# FMC_connector.net
KiCad netlist of a schematic drawn in Altium Designer
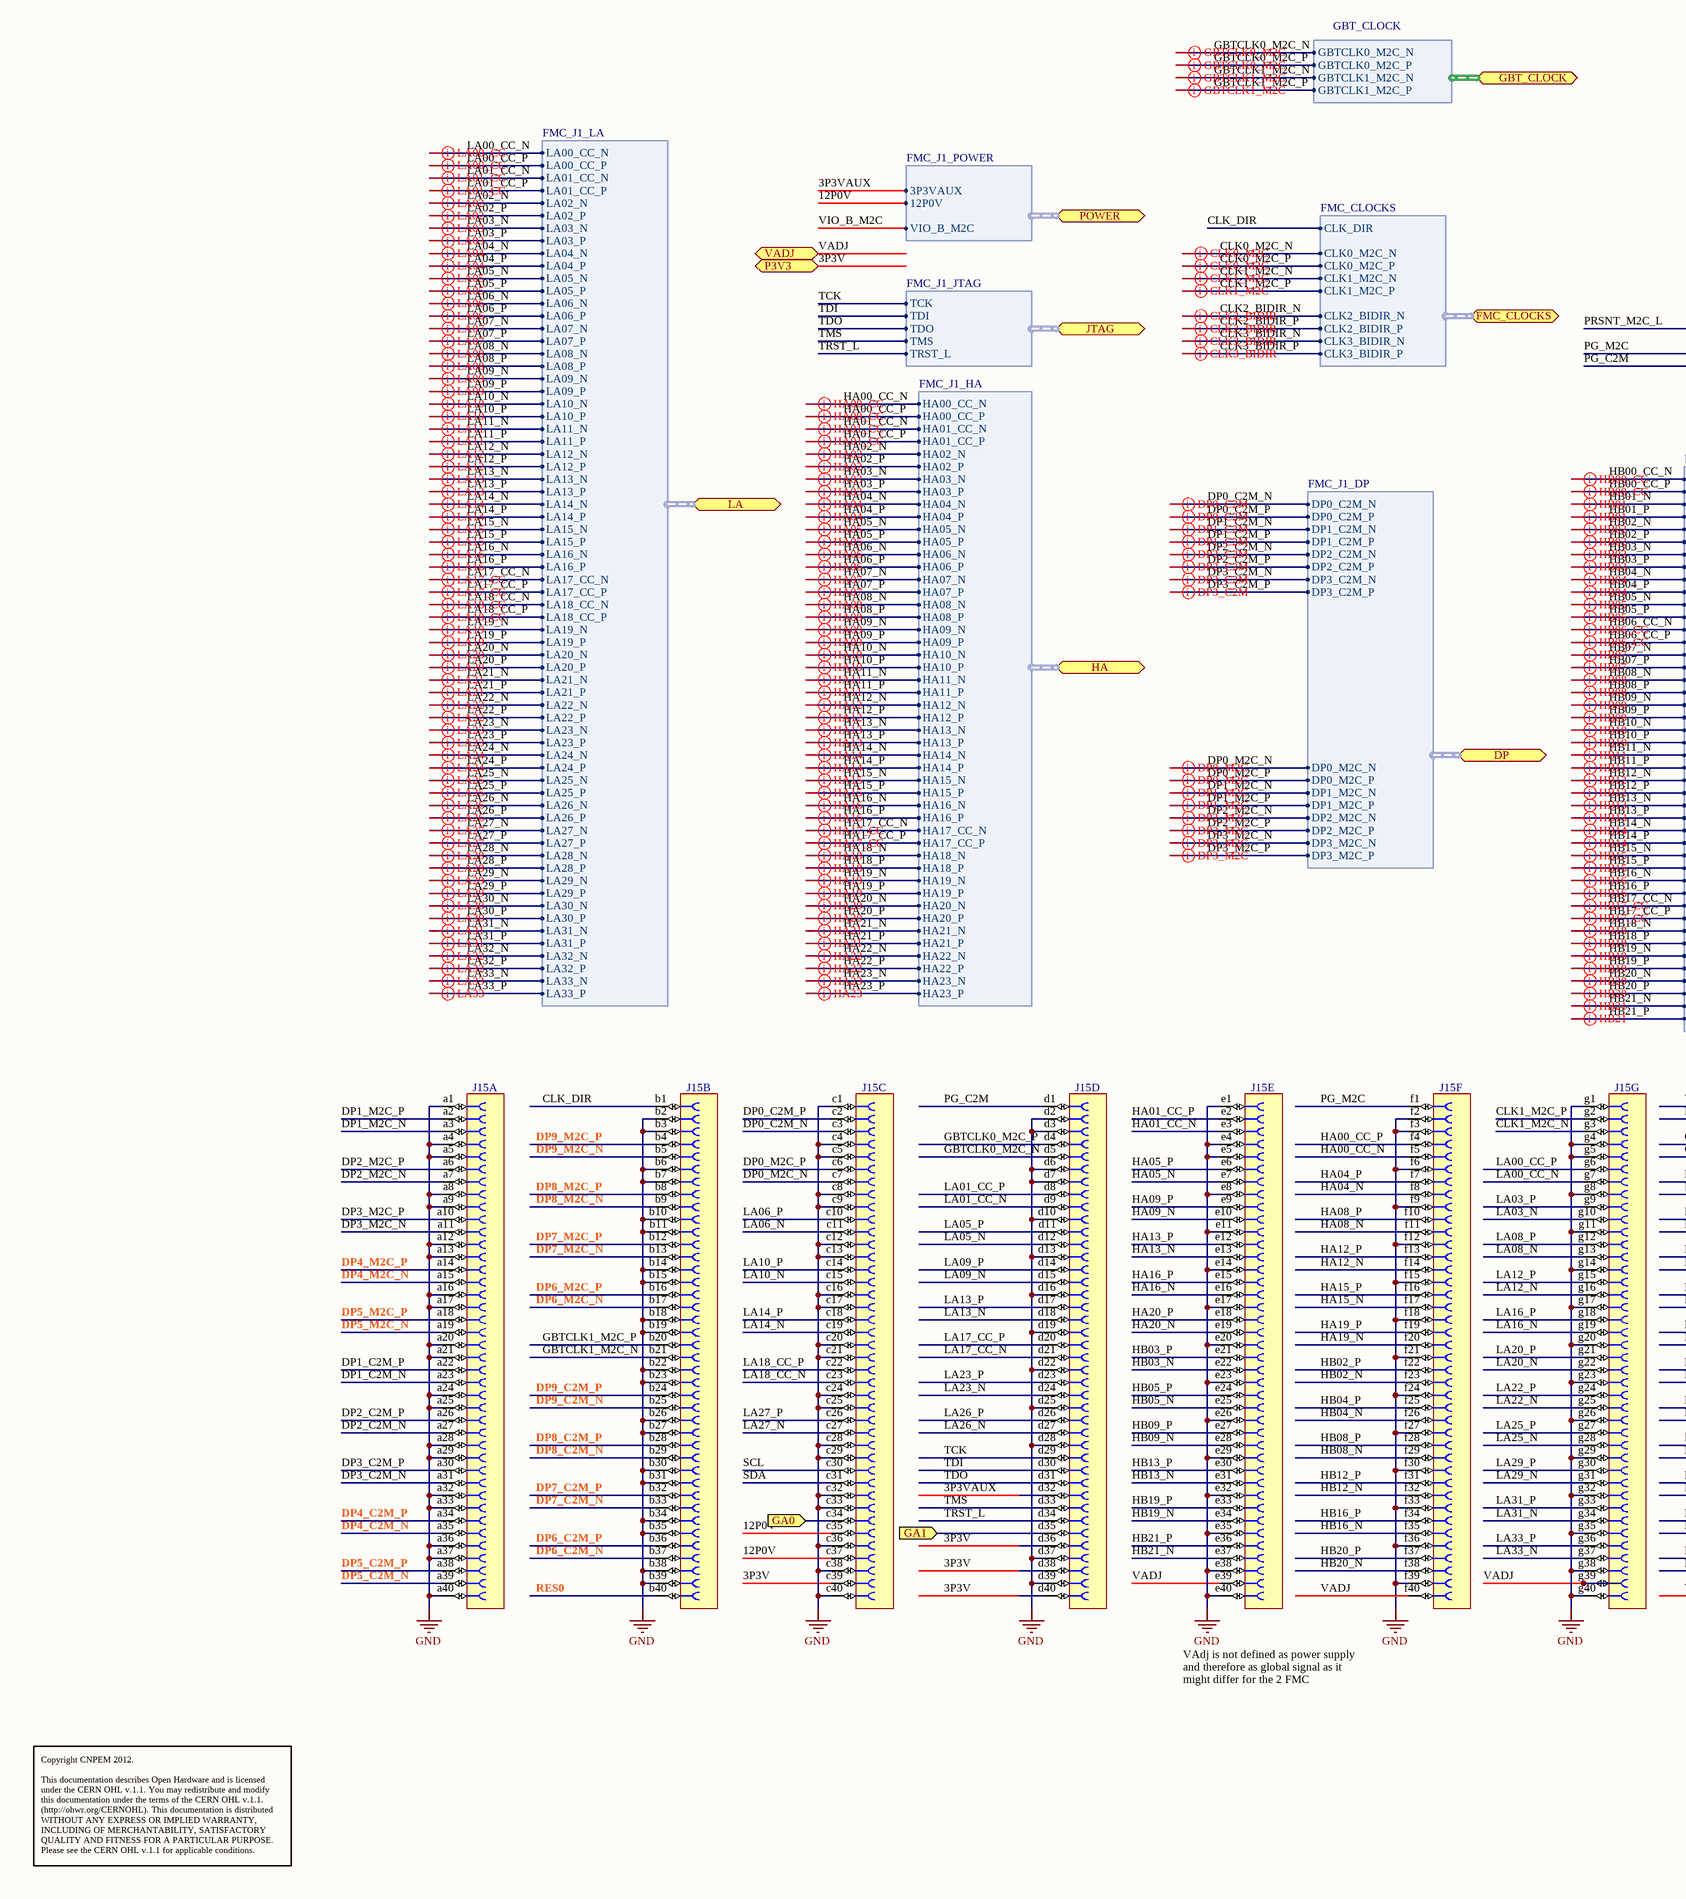
[diagram p0: FMC_connector.SchDoc, left]
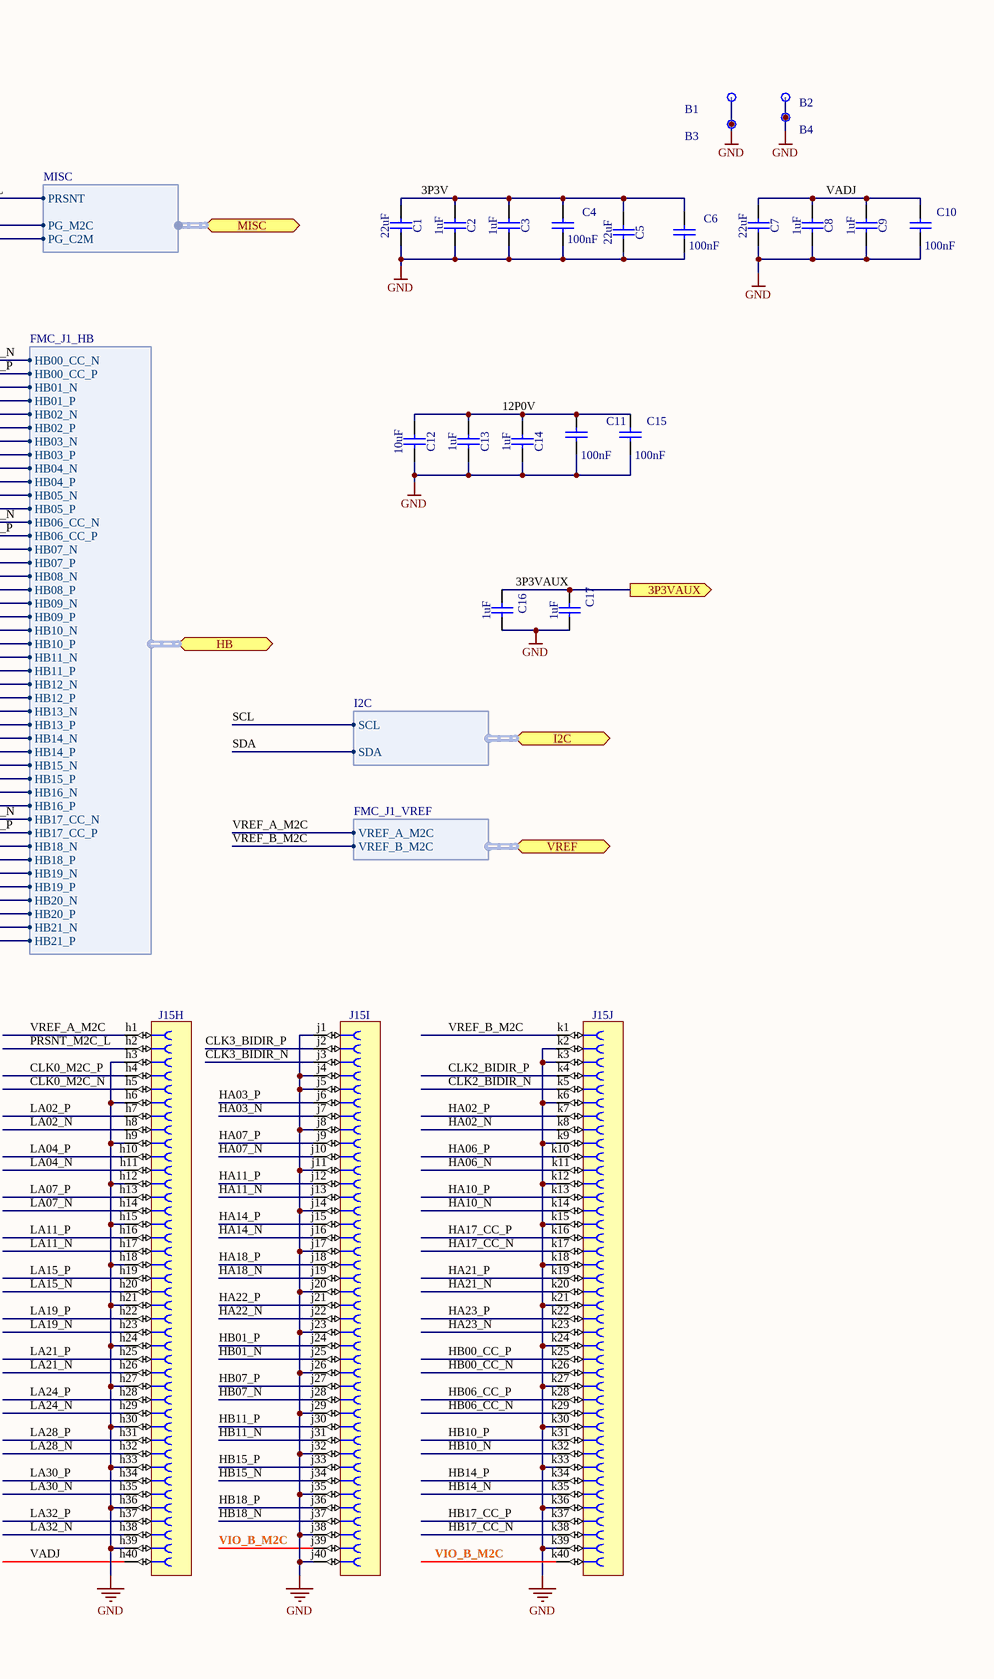
[diagram p1: FMC_connector.SchDoc, right]

(export (version "E")
  (design (tool "Eeschema 10.0.6"))
  (components
    (comp (ref "B1")
      (value "Plated Hole")
      (footprint "MTG270_500")
      (description "Single Terminal Socket")
      (fields (field (name "PART NUMBER") "PLATED_HOLE2.7_PAD5.0") (field (name "AUTHOR") "CERN DEM JMW"))
      (libsource (lib "Eletro-mechanical") (part "Single Terminal Socket"))
    )
    (comp (ref "B2")
      (value "Plated Hole")
      (footprint "MTG270_500")
      (description "Single Terminal Socket")
      (fields (field (name "PART NUMBER") "PLATED_HOLE2.7_PAD5.0") (field (name "AUTHOR") "CERN DEM JMW"))
      (libsource (lib "Eletro-mechanical") (part "Single Terminal Socket"))
    )
    (comp (ref "B3")
      (value "Plated Hole")
      (footprint "MTG270_500")
      (description "Single Terminal Socket")
      (fields (field (name "PART NUMBER") "PLATED_HOLE2.7_PAD5.0") (field (name "AUTHOR") "CERN DEM JMW"))
      (libsource (lib "Eletro-mechanical") (part "Single Terminal Socket"))
    )
    (comp (ref "B4")
      (value "Plated Hole")
      (footprint "MTG270_500")
      (description "Single Terminal Socket")
      (fields (field (name "PART NUMBER") "PLATED_HOLE2.7_PAD5.0") (field (name "AUTHOR") "CERN DEM JMW"))
      (libsource (lib "Eletro-mechanical") (part "Single Terminal Socket"))
    )
    (comp (ref "C1")
      (value "22uF")
      (footprint "CAPC3216X180N")
      (description "Non-polarised capacitor")
      (fields
        (field (name "PART NUMBER") "CC1206_22UF_10V_10%_X7R")
        (field (name "VOLTAGE") "10V")
        (field (name "AUTHOR") "CERN DEM JLC")
      )
      (libsource (lib "Capacitors") (part "Capacitor - non polarized"))
    )
    (comp (ref "C2")
      (value "1uF")
      (footprint "CAPC1608X87N")
      (description "Non-polarised capacitor")
      (fields
        (field (name "PART NUMBER") "CC0603_1UF_16V_10%_X7R")
        (field (name "VOLTAGE") "16V")
        (field (name "AUTHOR") "CERN DEM JLC")
      )
      (libsource (lib "Capacitors") (part "Capacitor - non polarized"))
    )
    (comp (ref "C3")
      (value "1uF")
      (footprint "CAPC1608X87N")
      (description "Non-polarised capacitor")
      (fields
        (field (name "PART NUMBER") "CC0603_1UF_16V_10%_X7R")
        (field (name "VOLTAGE") "16V")
        (field (name "AUTHOR") "CERN DEM JLC")
      )
      (libsource (lib "Capacitors") (part "Capacitor - non polarized"))
    )
    (comp (ref "C4")
      (value "100nF")
      (footprint "CAPC0603X33N")
      (description "Non-polarised capacitor")
      (fields
        (field (name "PART NUMBER") "CC0201_100NF_6.3V_10%_X5R")
        (field (name "VOLTAGE") "6.3V")
        (field (name "AUTHOR") "CERN DEM JLC")
      )
      (libsource (lib "Capacitors") (part "Capacitor - non polarized"))
    )
    (comp (ref "C5")
      (value "22uF")
      (footprint "CAPC3216X180N")
      (description "Non-polarised capacitor")
      (fields
        (field (name "PART NUMBER") "CC1206_22UF_10V_10%_X7R")
        (field (name "VOLTAGE") "10V")
        (field (name "AUTHOR") "CERN DEM JLC")
      )
      (libsource (lib "Capacitors") (part "Capacitor - non polarized"))
    )
    (comp (ref "C6")
      (value "100nF")
      (footprint "CAPC0603X33N")
      (description "Non-polarised capacitor")
      (fields
        (field (name "PART NUMBER") "CC0201_100NF_6.3V_10%_X5R")
        (field (name "VOLTAGE") "6.3V")
        (field (name "AUTHOR") "CERN DEM JLC")
      )
      (libsource (lib "Capacitors") (part "Capacitor - non polarized"))
    )
    (comp (ref "C7")
      (value "22uF")
      (footprint "CAPC3216X180N")
      (description "Non-polarised capacitor")
      (fields
        (field (name "PART NUMBER") "CC1206_22UF_10V_10%_X7R")
        (field (name "VOLTAGE") "10V")
        (field (name "AUTHOR") "CERN DEM JLC")
      )
      (libsource (lib "Capacitors") (part "Capacitor - non polarized"))
    )
    (comp (ref "C8")
      (value "1uF")
      (footprint "CAPC1608X87N")
      (description "Non-polarised capacitor")
      (fields
        (field (name "PART NUMBER") "CC0603_1UF_16V_10%_X7R")
        (field (name "VOLTAGE") "16V")
        (field (name "AUTHOR") "CERN DEM JLC")
      )
      (libsource (lib "Capacitors") (part "Capacitor - non polarized"))
    )
    (comp (ref "C9")
      (value "1uF")
      (footprint "CAPC1608X87N")
      (description "Non-polarised capacitor")
      (fields
        (field (name "PART NUMBER") "CC0603_1UF_16V_10%_X7R")
        (field (name "VOLTAGE") "16V")
        (field (name "AUTHOR") "CERN DEM JLC")
      )
      (libsource (lib "Capacitors") (part "Capacitor - non polarized"))
    )
    (comp (ref "C10")
      (value "100nF")
      (footprint "CAPC0603X33N")
      (description "Non-polarised capacitor")
      (fields
        (field (name "PART NUMBER") "CC0201_100NF_6.3V_10%_X5R")
        (field (name "VOLTAGE") "6.3V")
        (field (name "AUTHOR") "CERN DEM JLC")
      )
      (libsource (lib "Capacitors") (part "Capacitor - non polarized"))
    )
    (comp (ref "C11")
      (value "100nF")
      (footprint "CAPC0603X33N")
      (description "Non-polarised capacitor")
      (fields
        (field (name "PART NUMBER") "CC0201_100NF_6.3V_10%_X5R")
        (field (name "VOLTAGE") "6.3V")
        (field (name "AUTHOR") "CERN DEM JLC")
      )
      (libsource (lib "Capacitors") (part "Capacitor - non polarized"))
    )
    (comp (ref "C12")
      (value "10uF")
      (footprint "CAPC2012X135N")
      (description "Non-polarised capacitor")
      (fields
        (field (name "PART NUMBER") "CC0805_10UF_16V_10%_X5R")
        (field (name "VOLTAGE") "16V")
        (field (name "AUTHOR") "CERN DEM JLC")
      )
      (libsource (lib "Capacitors") (part "Capacitor - non polarized"))
    )
    (comp (ref "C13")
      (value "1uF")
      (footprint "CAPC1608X87N")
      (description "Non-polarised capacitor")
      (fields
        (field (name "PART NUMBER") "CC0603_1UF_16V_10%_X7R")
        (field (name "VOLTAGE") "16V")
        (field (name "AUTHOR") "CERN DEM JLC")
      )
      (libsource (lib "Capacitors") (part "Capacitor - non polarized"))
    )
    (comp (ref "C14")
      (value "1uF")
      (footprint "CAPC1608X87N")
      (description "Non-polarised capacitor")
      (fields
        (field (name "PART NUMBER") "CC0603_1UF_16V_10%_X7R")
        (field (name "VOLTAGE") "16V")
        (field (name "AUTHOR") "CERN DEM JLC")
      )
      (libsource (lib "Capacitors") (part "Capacitor - non polarized"))
    )
    (comp (ref "C15")
      (value "100nF")
      (footprint "CAPC0603X33N")
      (description "Non-polarised capacitor")
      (fields
        (field (name "PART NUMBER") "CC0201_100NF_6.3V_10%_X5R")
        (field (name "VOLTAGE") "6.3V")
        (field (name "AUTHOR") "CERN DEM JLC")
      )
      (libsource (lib "Capacitors") (part "Capacitor - non polarized"))
    )
    (comp (ref "C16")
      (value "1uF")
      (footprint "CAPC1608X87N")
      (description "Non-polarised capacitor")
      (fields
        (field (name "PART NUMBER") "CC0603_1UF_16V_10%_X7R")
        (field (name "VOLTAGE") "16V")
        (field (name "AUTHOR") "CERN DEM JLC")
      )
      (libsource (lib "Capacitors") (part "Capacitor - non polarized"))
    )
    (comp (ref "C17")
      (value "1uF")
      (footprint "CAPC1608X87N")
      (description "Non-polarised capacitor")
      (fields
        (field (name "PART NUMBER") "CC0603_1UF_16V_10%_X7R")
        (field (name "VOLTAGE") "16V")
        (field (name "AUTHOR") "CERN DEM JLC")
      )
      (libsource (lib "Capacitors") (part "Capacitor - non polarized"))
    )
    (comp (ref "J15")
      (value "VITA 57")
      (footprint "SAMTEC_ASP-134486-01")
      (description "Connector VITA 57, 400 Female contacts in 10 row abcdefghj")
      (fields
        (field (name "PART NUMBER") "SAMTEC_ASP-134486-01")
        (field (name "MANUFACTURER") "SAMTEC")
        (field (name "AUTHOR") "CERN DEM JLC")
      )
      (libsource (lib "Connectors") (part "Connector VITA 57 400 Female (abcdefghjk)"))
    )
  )
  (nets
    (net (code "12") (name "/3P3V") (class "Default")
      (node (ref "C1") (pin "1") (pinfunction "1_1") (pintype "passive"))
      (node (ref "C2") (pin "1") (pinfunction "1_1") (pintype "passive"))
      (node (ref "C3") (pin "1") (pinfunction "1_1") (pintype "passive"))
      (node (ref "C4") (pin "2") (pinfunction "2_2") (pintype "passive"))
      (node (ref "C5") (pin "1") (pinfunction "1_1") (pintype "passive"))
      (node (ref "C6") (pin "2") (pinfunction "2_2") (pintype "passive"))
      (node (ref "J15") (pin "c39") (pinfunction "c39_c39") (pintype "bidirectional"))
      (node (ref "J15") (pin "d36") (pinfunction "d36_d36") (pintype "bidirectional"))
      (node (ref "J15") (pin "d38") (pinfunction "d38_d38") (pintype "bidirectional"))
      (node (ref "J15") (pin "d40") (pinfunction "d40_d40") (pintype "bidirectional"))
    )
    (net (code "13") (name "/3P3VAUX") (class "Default")
      (node (ref "C16") (pin "1") (pinfunction "1_1") (pintype "passive"))
      (node (ref "C17") (pin "1") (pinfunction "1_1") (pintype "passive"))
      (node (ref "J15") (pin "d32") (pinfunction "d32_d32") (pintype "bidirectional"))
    )
    (net (code "14") (name "/12P0V") (class "Default")
      (node (ref "C11") (pin "2") (pinfunction "2_2") (pintype "passive"))
      (node (ref "C12") (pin "1") (pinfunction "1_1") (pintype "passive"))
      (node (ref "C13") (pin "1") (pinfunction "1_1") (pintype "passive"))
      (node (ref "C14") (pin "1") (pinfunction "1_1") (pintype "passive"))
      (node (ref "C15") (pin "2") (pinfunction "2_2") (pintype "passive"))
      (node (ref "J15") (pin "c35") (pinfunction "c35_c35") (pintype "bidirectional"))
      (node (ref "J15") (pin "c37") (pinfunction "c37_c37") (pintype "bidirectional"))
    )
    (net (code "15") (name "/CLK0_M2C_N") (class "Default")
      (node (ref "J15") (pin "h5") (pinfunction "h5_h5") (pintype "bidirectional"))
    )
    (net (code "16") (name "/CLK0_M2C_P") (class "Default")
      (node (ref "J15") (pin "h4") (pinfunction "h4_h4") (pintype "bidirectional"))
    )
    (net (code "17") (name "/CLK1_M2C_N") (class "Default")
      (node (ref "J15") (pin "g3") (pinfunction "g3_g3") (pintype "bidirectional"))
    )
    (net (code "18") (name "/CLK1_M2C_P") (class "Default")
      (node (ref "J15") (pin "g2") (pinfunction "g2_g2") (pintype "bidirectional"))
    )
    (net (code "19") (name "/CLK2_BIDIR_N") (class "Default")
      (node (ref "J15") (pin "k5") (pinfunction "k5_k5") (pintype "bidirectional"))
    )
    (net (code "20") (name "/CLK2_BIDIR_P") (class "Default")
      (node (ref "J15") (pin "k4") (pinfunction "k4_k4") (pintype "bidirectional"))
    )
    (net (code "21") (name "/CLK3_BIDIR_N") (class "Default")
      (node (ref "J15") (pin "j3") (pinfunction "j3_j3") (pintype "bidirectional"))
    )
    (net (code "22") (name "/CLK3_BIDIR_P") (class "Default")
      (node (ref "J15") (pin "j2") (pinfunction "j2_j2") (pintype "bidirectional"))
    )
    (net (code "23") (name "/CLK_DIR") (class "Default")
      (node (ref "J15") (pin "b1") (pinfunction "b1_b1") (pintype "bidirectional"))
    )
    (net (code "24") (name "/DP0_C2M_N") (class "Default")
      (node (ref "J15") (pin "c3") (pinfunction "c3_c3") (pintype "bidirectional"))
    )
    (net (code "25") (name "/DP0_C2M_P") (class "Default")
      (node (ref "J15") (pin "c2") (pinfunction "c2_c2") (pintype "bidirectional"))
    )
    (net (code "26") (name "/DP0_M2C_N") (class "Default")
      (node (ref "J15") (pin "c7") (pinfunction "c7_c7") (pintype "bidirectional"))
    )
    (net (code "27") (name "/DP0_M2C_P") (class "Default")
      (node (ref "J15") (pin "c6") (pinfunction "c6_c6") (pintype "bidirectional"))
    )
    (net (code "28") (name "/DP1_C2M_N") (class "Default")
      (node (ref "J15") (pin "a23") (pinfunction "a23_a23") (pintype "bidirectional"))
    )
    (net (code "29") (name "/DP1_C2M_P") (class "Default")
      (node (ref "J15") (pin "a22") (pinfunction "a22_a22") (pintype "bidirectional"))
    )
    (net (code "30") (name "/DP1_M2C_N") (class "Default")
      (node (ref "J15") (pin "a3") (pinfunction "a3_a3") (pintype "bidirectional"))
    )
    (net (code "31") (name "/DP1_M2C_P") (class "Default")
      (node (ref "J15") (pin "a2") (pinfunction "a2_a2") (pintype "bidirectional"))
    )
    (net (code "32") (name "/DP2_C2M_N") (class "Default")
      (node (ref "J15") (pin "a27") (pinfunction "a27_a27") (pintype "bidirectional"))
    )
    (net (code "33") (name "/DP2_C2M_P") (class "Default")
      (node (ref "J15") (pin "a26") (pinfunction "a26_a26") (pintype "bidirectional"))
    )
    (net (code "34") (name "/DP2_M2C_N") (class "Default")
      (node (ref "J15") (pin "a7") (pinfunction "a7_a7") (pintype "bidirectional"))
    )
    (net (code "35") (name "/DP2_M2C_P") (class "Default")
      (node (ref "J15") (pin "a6") (pinfunction "a6_a6") (pintype "bidirectional"))
    )
    (net (code "36") (name "/DP3_C2M_N") (class "Default")
      (node (ref "J15") (pin "a31") (pinfunction "a31_a31") (pintype "bidirectional"))
    )
    (net (code "37") (name "/DP3_C2M_P") (class "Default")
      (node (ref "J15") (pin "a30") (pinfunction "a30_a30") (pintype "bidirectional"))
    )
    (net (code "38") (name "/DP3_M2C_N") (class "Default")
      (node (ref "J15") (pin "a11") (pinfunction "a11_a11") (pintype "bidirectional"))
    )
    (net (code "39") (name "/DP3_M2C_P") (class "Default")
      (node (ref "J15") (pin "a10") (pinfunction "a10_a10") (pintype "bidirectional"))
    )
    (net (code "40") (name "/GA0") (class "Default")
      (node (ref "J15") (pin "c34") (pinfunction "c34_c34") (pintype "bidirectional"))
    )
    (net (code "41") (name "/GA1") (class "Default")
      (node (ref "J15") (pin "d35") (pinfunction "d35_d35") (pintype "bidirectional"))
    )
    (net (code "42") (name "/GBTCLK0_M2C_N") (class "Default")
      (node (ref "J15") (pin "d5") (pinfunction "d5_d5") (pintype "bidirectional"))
    )
    (net (code "43") (name "/GBTCLK0_M2C_P") (class "Default")
      (node (ref "J15") (pin "d4") (pinfunction "d4_d4") (pintype "bidirectional"))
    )
    (net (code "44") (name "/GBTCLK1_M2C_N") (class "Default")
      (node (ref "J15") (pin "b21") (pinfunction "b21_b21") (pintype "bidirectional"))
    )
    (net (code "45") (name "/GBTCLK1_M2C_P") (class "Default")
      (node (ref "J15") (pin "b20") (pinfunction "b20_b20") (pintype "bidirectional"))
    )
    (net (code "46") (name "/HA00_CC_N") (class "Default")
      (node (ref "J15") (pin "f5") (pinfunction "f5_f5") (pintype "bidirectional"))
    )
    (net (code "47") (name "/HA00_CC_P") (class "Default")
      (node (ref "J15") (pin "f4") (pinfunction "f4_f4") (pintype "bidirectional"))
    )
    (net (code "48") (name "/HA01_CC_N") (class "Default")
      (node (ref "J15") (pin "e3") (pinfunction "e3_e3") (pintype "bidirectional"))
    )
    (net (code "49") (name "/HA01_CC_P") (class "Default")
      (node (ref "J15") (pin "e2") (pinfunction "e2_e2") (pintype "bidirectional"))
    )
    (net (code "50") (name "/HA02_N") (class "Default")
      (node (ref "J15") (pin "k8") (pinfunction "k8_k8") (pintype "bidirectional"))
    )
    (net (code "51") (name "/HA02_P") (class "Default")
      (node (ref "J15") (pin "k7") (pinfunction "k7_k7") (pintype "bidirectional"))
    )
    (net (code "52") (name "/HA03_N") (class "Default")
      (node (ref "J15") (pin "j7") (pinfunction "j7_j7") (pintype "bidirectional"))
    )
    (net (code "53") (name "/HA03_P") (class "Default")
      (node (ref "J15") (pin "j6") (pinfunction "j6_j6") (pintype "bidirectional"))
    )
    (net (code "54") (name "/HA04_N") (class "Default")
      (node (ref "J15") (pin "f8") (pinfunction "f8_f8") (pintype "bidirectional"))
    )
    (net (code "55") (name "/HA04_P") (class "Default")
      (node (ref "J15") (pin "f7") (pinfunction "f7_f7") (pintype "bidirectional"))
    )
    (net (code "56") (name "/HA05_N") (class "Default")
      (node (ref "J15") (pin "e7") (pinfunction "e7_e7") (pintype "bidirectional"))
    )
    (net (code "57") (name "/HA05_P") (class "Default")
      (node (ref "J15") (pin "e6") (pinfunction "e6_e6") (pintype "bidirectional"))
    )
    (net (code "58") (name "/HA06_N") (class "Default")
      (node (ref "J15") (pin "k11") (pinfunction "k11_k11") (pintype "bidirectional"))
    )
    (net (code "59") (name "/HA06_P") (class "Default")
      (node (ref "J15") (pin "k10") (pinfunction "k10_k10") (pintype "bidirectional"))
    )
    (net (code "60") (name "/HA07_N") (class "Default")
      (node (ref "J15") (pin "j10") (pinfunction "j10_j10") (pintype "bidirectional"))
    )
    (net (code "61") (name "/HA07_P") (class "Default")
      (node (ref "J15") (pin "j9") (pinfunction "j9_j9") (pintype "bidirectional"))
    )
    (net (code "62") (name "/HA08_N") (class "Default")
      (node (ref "J15") (pin "f11") (pinfunction "f11_f11") (pintype "bidirectional"))
    )
    (net (code "63") (name "/HA08_P") (class "Default")
      (node (ref "J15") (pin "f10") (pinfunction "f10_f10") (pintype "bidirectional"))
    )
    (net (code "64") (name "/HA09_N") (class "Default")
      (node (ref "J15") (pin "e10") (pinfunction "e10_e10") (pintype "bidirectional"))
    )
    (net (code "65") (name "/HA09_P") (class "Default")
      (node (ref "J15") (pin "e9") (pinfunction "e9_e9") (pintype "bidirectional"))
    )
    (net (code "66") (name "/HA10_N") (class "Default")
      (node (ref "J15") (pin "k14") (pinfunction "k14_k14") (pintype "bidirectional"))
    )
    (net (code "67") (name "/HA10_P") (class "Default")
      (node (ref "J15") (pin "k13") (pinfunction "k13_k13") (pintype "bidirectional"))
    )
    (net (code "68") (name "/HA11_N") (class "Default")
      (node (ref "J15") (pin "j13") (pinfunction "j13_j13") (pintype "bidirectional"))
    )
    (net (code "69") (name "/HA11_P") (class "Default")
      (node (ref "J15") (pin "j12") (pinfunction "j12_j12") (pintype "bidirectional"))
    )
    (net (code "70") (name "/HA12_N") (class "Default")
      (node (ref "J15") (pin "f14") (pinfunction "f14_f14") (pintype "bidirectional"))
    )
    (net (code "71") (name "/HA12_P") (class "Default")
      (node (ref "J15") (pin "f13") (pinfunction "f13_f13") (pintype "bidirectional"))
    )
    (net (code "72") (name "/HA13_N") (class "Default")
      (node (ref "J15") (pin "e13") (pinfunction "e13_e13") (pintype "bidirectional"))
    )
    (net (code "73") (name "/HA13_P") (class "Default")
      (node (ref "J15") (pin "e12") (pinfunction "e12_e12") (pintype "bidirectional"))
    )
    (net (code "74") (name "/HA14_N") (class "Default")
      (node (ref "J15") (pin "j16") (pinfunction "j16_j16") (pintype "bidirectional"))
    )
    (net (code "75") (name "/HA14_P") (class "Default")
      (node (ref "J15") (pin "j15") (pinfunction "j15_j15") (pintype "bidirectional"))
    )
    (net (code "76") (name "/HA15_N") (class "Default")
      (node (ref "J15") (pin "f17") (pinfunction "f17_f17") (pintype "bidirectional"))
    )
    (net (code "77") (name "/HA15_P") (class "Default")
      (node (ref "J15") (pin "f16") (pinfunction "f16_f16") (pintype "bidirectional"))
    )
    (net (code "78") (name "/HA16_N") (class "Default")
      (node (ref "J15") (pin "e16") (pinfunction "e16_e16") (pintype "bidirectional"))
    )
    (net (code "79") (name "/HA16_P") (class "Default")
      (node (ref "J15") (pin "e15") (pinfunction "e15_e15") (pintype "bidirectional"))
    )
    (net (code "80") (name "/HA17_CC_N") (class "Default")
      (node (ref "J15") (pin "k17") (pinfunction "k17_k17") (pintype "bidirectional"))
    )
    (net (code "81") (name "/HA17_CC_P") (class "Default")
      (node (ref "J15") (pin "k16") (pinfunction "k16_k16") (pintype "bidirectional"))
    )
    (net (code "82") (name "/HA18_N") (class "Default")
      (node (ref "J15") (pin "j19") (pinfunction "j19_j19") (pintype "bidirectional"))
    )
    (net (code "83") (name "/HA18_P") (class "Default")
      (node (ref "J15") (pin "j18") (pinfunction "j18_j18") (pintype "bidirectional"))
    )
    (net (code "84") (name "/HA19_N") (class "Default")
      (node (ref "J15") (pin "f20") (pinfunction "f20_f20") (pintype "bidirectional"))
    )
    (net (code "85") (name "/HA19_P") (class "Default")
      (node (ref "J15") (pin "f19") (pinfunction "f19_f19") (pintype "bidirectional"))
    )
    (net (code "86") (name "/HA20_N") (class "Default")
      (node (ref "J15") (pin "e19") (pinfunction "e19_e19") (pintype "bidirectional"))
    )
    (net (code "87") (name "/HA20_P") (class "Default")
      (node (ref "J15") (pin "e18") (pinfunction "e18_e18") (pintype "bidirectional"))
    )
    (net (code "88") (name "/HA21_N") (class "Default")
      (node (ref "J15") (pin "k20") (pinfunction "k20_k20") (pintype "bidirectional"))
    )
    (net (code "89") (name "/HA21_P") (class "Default")
      (node (ref "J15") (pin "k19") (pinfunction "k19_k19") (pintype "bidirectional"))
    )
    (net (code "90") (name "/HA22_N") (class "Default")
      (node (ref "J15") (pin "j22") (pinfunction "j22_j22") (pintype "bidirectional"))
    )
    (net (code "91") (name "/HA22_P") (class "Default")
      (node (ref "J15") (pin "j21") (pinfunction "j21_j21") (pintype "bidirectional"))
    )
    (net (code "92") (name "/HA23_N") (class "Default")
      (node (ref "J15") (pin "k23") (pinfunction "k23_k23") (pintype "bidirectional"))
    )
    (net (code "93") (name "/HA23_P") (class "Default")
      (node (ref "J15") (pin "k22") (pinfunction "k22_k22") (pintype "bidirectional"))
    )
    (net (code "94") (name "/HB00_CC_N") (class "Default")
      (node (ref "J15") (pin "k26") (pinfunction "k26_k26") (pintype "bidirectional"))
    )
    (net (code "95") (name "/HB00_CC_P") (class "Default")
      (node (ref "J15") (pin "k25") (pinfunction "k25_k25") (pintype "bidirectional"))
    )
    (net (code "96") (name "/HB01_N") (class "Default")
      (node (ref "J15") (pin "j25") (pinfunction "j25_j25") (pintype "bidirectional"))
    )
    (net (code "97") (name "/HB01_P") (class "Default")
      (node (ref "J15") (pin "j24") (pinfunction "j24_j24") (pintype "bidirectional"))
    )
    (net (code "98") (name "/HB02_N") (class "Default")
      (node (ref "J15") (pin "f23") (pinfunction "f23_f23") (pintype "bidirectional"))
    )
    (net (code "99") (name "/HB02_P") (class "Default")
      (node (ref "J15") (pin "f22") (pinfunction "f22_f22") (pintype "bidirectional"))
    )
    (net (code "100") (name "/HB03_N") (class "Default")
      (node (ref "J15") (pin "e22") (pinfunction "e22_e22") (pintype "bidirectional"))
    )
    (net (code "101") (name "/HB03_P") (class "Default")
      (node (ref "J15") (pin "e21") (pinfunction "e21_e21") (pintype "bidirectional"))
    )
    (net (code "102") (name "/HB04_N") (class "Default")
      (node (ref "J15") (pin "f26") (pinfunction "f26_f26") (pintype "bidirectional"))
    )
    (net (code "103") (name "/HB04_P") (class "Default")
      (node (ref "J15") (pin "f25") (pinfunction "f25_f25") (pintype "bidirectional"))
    )
    (net (code "104") (name "/HB05_N") (class "Default")
      (node (ref "J15") (pin "e25") (pinfunction "e25_e25") (pintype "bidirectional"))
    )
    (net (code "105") (name "/HB05_P") (class "Default")
      (node (ref "J15") (pin "e24") (pinfunction "e24_e24") (pintype "bidirectional"))
    )
    (net (code "106") (name "/HB06_CC_N") (class "Default")
      (node (ref "J15") (pin "k29") (pinfunction "k29_k29") (pintype "bidirectional"))
    )
    (net (code "107") (name "/HB06_CC_P") (class "Default")
      (node (ref "J15") (pin "k28") (pinfunction "k28_k28") (pintype "bidirectional"))
    )
    (net (code "108") (name "/HB07_N") (class "Default")
      (node (ref "J15") (pin "j28") (pinfunction "j28_j28") (pintype "bidirectional"))
    )
    (net (code "109") (name "/HB07_P") (class "Default")
      (node (ref "J15") (pin "j27") (pinfunction "j27_j27") (pintype "bidirectional"))
    )
    (net (code "110") (name "/HB08_N") (class "Default")
      (node (ref "J15") (pin "f29") (pinfunction "f29_f29") (pintype "bidirectional"))
    )
    (net (code "111") (name "/HB08_P") (class "Default")
      (node (ref "J15") (pin "f28") (pinfunction "f28_f28") (pintype "bidirectional"))
    )
    (net (code "112") (name "/HB09_N") (class "Default")
      (node (ref "J15") (pin "e28") (pinfunction "e28_e28") (pintype "bidirectional"))
    )
    (net (code "113") (name "/HB09_P") (class "Default")
      (node (ref "J15") (pin "e27") (pinfunction "e27_e27") (pintype "bidirectional"))
    )
    (net (code "114") (name "/HB10_N") (class "Default")
      (node (ref "J15") (pin "k32") (pinfunction "k32_k32") (pintype "bidirectional"))
    )
    (net (code "115") (name "/HB10_P") (class "Default")
      (node (ref "J15") (pin "k31") (pinfunction "k31_k31") (pintype "bidirectional"))
    )
    (net (code "116") (name "/HB11_N") (class "Default")
      (node (ref "J15") (pin "j31") (pinfunction "j31_j31") (pintype "bidirectional"))
    )
    (net (code "117") (name "/HB11_P") (class "Default")
      (node (ref "J15") (pin "j30") (pinfunction "j30_j30") (pintype "bidirectional"))
    )
    (net (code "118") (name "/HB12_N") (class "Default")
      (node (ref "J15") (pin "f32") (pinfunction "f32_f32") (pintype "bidirectional"))
    )
    (net (code "119") (name "/HB12_P") (class "Default")
      (node (ref "J15") (pin "f31") (pinfunction "f31_f31") (pintype "bidirectional"))
    )
    (net (code "120") (name "/HB13_N") (class "Default")
      (node (ref "J15") (pin "e31") (pinfunction "e31_e31") (pintype "bidirectional"))
    )
    (net (code "121") (name "/HB13_P") (class "Default")
      (node (ref "J15") (pin "e30") (pinfunction "e30_e30") (pintype "bidirectional"))
    )
    (net (code "122") (name "/HB14_N") (class "Default")
      (node (ref "J15") (pin "k35") (pinfunction "k35_k35") (pintype "bidirectional"))
    )
    (net (code "123") (name "/HB14_P") (class "Default")
      (node (ref "J15") (pin "k34") (pinfunction "k34_k34") (pintype "bidirectional"))
    )
    (net (code "124") (name "/HB15_N") (class "Default")
      (node (ref "J15") (pin "j34") (pinfunction "j34_j34") (pintype "bidirectional"))
    )
    (net (code "125") (name "/HB15_P") (class "Default")
      (node (ref "J15") (pin "j33") (pinfunction "j33_j33") (pintype "bidirectional"))
    )
    (net (code "126") (name "/HB16_N") (class "Default")
      (node (ref "J15") (pin "f35") (pinfunction "f35_f35") (pintype "bidirectional"))
    )
    (net (code "127") (name "/HB16_P") (class "Default")
      (node (ref "J15") (pin "f34") (pinfunction "f34_f34") (pintype "bidirectional"))
    )
    (net (code "128") (name "/HB17_CC_N") (class "Default")
      (node (ref "J15") (pin "k38") (pinfunction "k38_k38") (pintype "bidirectional"))
    )
    (net (code "129") (name "/HB17_CC_P") (class "Default")
      (node (ref "J15") (pin "k37") (pinfunction "k37_k37") (pintype "bidirectional"))
    )
    (net (code "130") (name "/HB18_N") (class "Default")
      (node (ref "J15") (pin "j37") (pinfunction "j37_j37") (pintype "bidirectional"))
    )
    (net (code "131") (name "/HB18_P") (class "Default")
      (node (ref "J15") (pin "j36") (pinfunction "j36_j36") (pintype "bidirectional"))
    )
    (net (code "132") (name "/HB19_N") (class "Default")
      (node (ref "J15") (pin "e34") (pinfunction "e34_e34") (pintype "bidirectional"))
    )
    (net (code "133") (name "/HB19_P") (class "Default")
      (node (ref "J15") (pin "e33") (pinfunction "e33_e33") (pintype "bidirectional"))
    )
    (net (code "134") (name "/HB20_N") (class "Default")
      (node (ref "J15") (pin "f38") (pinfunction "f38_f38") (pintype "bidirectional"))
    )
    (net (code "135") (name "/HB20_P") (class "Default")
      (node (ref "J15") (pin "f37") (pinfunction "f37_f37") (pintype "bidirectional"))
    )
    (net (code "136") (name "/HB21_N") (class "Default")
      (node (ref "J15") (pin "e37") (pinfunction "e37_e37") (pintype "bidirectional"))
    )
    (net (code "137") (name "/HB21_P") (class "Default")
      (node (ref "J15") (pin "e36") (pinfunction "e36_e36") (pintype "bidirectional"))
    )
    (net (code "138") (name "/LA00_CC_N") (class "Default")
      (node (ref "J15") (pin "g7") (pinfunction "g7_g7") (pintype "bidirectional"))
    )
    (net (code "139") (name "/LA00_CC_P") (class "Default")
      (node (ref "J15") (pin "g6") (pinfunction "g6_g6") (pintype "bidirectional"))
    )
    (net (code "140") (name "/LA01_CC_N") (class "Default")
      (node (ref "J15") (pin "d9") (pinfunction "d9_d9") (pintype "bidirectional"))
    )
    (net (code "141") (name "/LA01_CC_P") (class "Default")
      (node (ref "J15") (pin "d8") (pinfunction "d8_d8") (pintype "bidirectional"))
    )
    (net (code "142") (name "/LA02_N") (class "Default")
      (node (ref "J15") (pin "h8") (pinfunction "h8_h8") (pintype "bidirectional"))
    )
    (net (code "143") (name "/LA02_P") (class "Default")
      (node (ref "J15") (pin "h7") (pinfunction "h7_h7") (pintype "bidirectional"))
    )
    (net (code "144") (name "/LA03_N") (class "Default")
      (node (ref "J15") (pin "g10") (pinfunction "g10_g10") (pintype "bidirectional"))
    )
    (net (code "145") (name "/LA03_P") (class "Default")
      (node (ref "J15") (pin "g9") (pinfunction "g9_g9") (pintype "bidirectional"))
    )
    (net (code "146") (name "/LA04_N") (class "Default")
      (node (ref "J15") (pin "h11") (pinfunction "h11_h11") (pintype "bidirectional"))
    )
    (net (code "147") (name "/LA04_P") (class "Default")
      (node (ref "J15") (pin "h10") (pinfunction "h10_h10") (pintype "bidirectional"))
    )
    (net (code "148") (name "/LA05_N") (class "Default")
      (node (ref "J15") (pin "d12") (pinfunction "d12_d12") (pintype "bidirectional"))
    )
    (net (code "149") (name "/LA05_P") (class "Default")
      (node (ref "J15") (pin "d11") (pinfunction "d11_d11") (pintype "bidirectional"))
    )
    (net (code "150") (name "/LA06_N") (class "Default")
      (node (ref "J15") (pin "c11") (pinfunction "c11_c11") (pintype "bidirectional"))
    )
    (net (code "151") (name "/LA06_P") (class "Default")
      (node (ref "J15") (pin "c10") (pinfunction "c10_c10") (pintype "bidirectional"))
    )
    (net (code "152") (name "/LA07_N") (class "Default")
      (node (ref "J15") (pin "h14") (pinfunction "h14_h14") (pintype "bidirectional"))
    )
    (net (code "153") (name "/LA07_P") (class "Default")
      (node (ref "J15") (pin "h13") (pinfunction "h13_h13") (pintype "bidirectional"))
    )
    (net (code "154") (name "/LA08_N") (class "Default")
      (node (ref "J15") (pin "g13") (pinfunction "g13_g13") (pintype "bidirectional"))
    )
    (net (code "155") (name "/LA08_P") (class "Default")
      (node (ref "J15") (pin "g12") (pinfunction "g12_g12") (pintype "bidirectional"))
    )
    (net (code "156") (name "/LA09_N") (class "Default")
      (node (ref "J15") (pin "d15") (pinfunction "d15_d15") (pintype "bidirectional"))
    )
    (net (code "157") (name "/LA09_P") (class "Default")
      (node (ref "J15") (pin "d14") (pinfunction "d14_d14") (pintype "bidirectional"))
    )
    (net (code "158") (name "/LA10_N") (class "Default")
      (node (ref "J15") (pin "c15") (pinfunction "c15_c15") (pintype "bidirectional"))
    )
    (net (code "159") (name "/LA10_P") (class "Default")
      (node (ref "J15") (pin "c14") (pinfunction "c14_c14") (pintype "bidirectional"))
    )
    (net (code "160") (name "/LA11_N") (class "Default")
      (node (ref "J15") (pin "h17") (pinfunction "h17_h17") (pintype "bidirectional"))
    )
    (net (code "161") (name "/LA11_P") (class "Default")
      (node (ref "J15") (pin "h16") (pinfunction "h16_h16") (pintype "bidirectional"))
    )
    (net (code "162") (name "/LA12_N") (class "Default")
      (node (ref "J15") (pin "g16") (pinfunction "g16_g16") (pintype "bidirectional"))
    )
    (net (code "163") (name "/LA12_P") (class "Default")
      (node (ref "J15") (pin "g15") (pinfunction "g15_g15") (pintype "bidirectional"))
    )
    (net (code "164") (name "/LA13_N") (class "Default")
      (node (ref "J15") (pin "d18") (pinfunction "d18_d18") (pintype "bidirectional"))
    )
    (net (code "165") (name "/LA13_P") (class "Default")
      (node (ref "J15") (pin "d17") (pinfunction "d17_d17") (pintype "bidirectional"))
    )
    (net (code "166") (name "/LA14_N") (class "Default")
      (node (ref "J15") (pin "c19") (pinfunction "c19_c19") (pintype "bidirectional"))
    )
    (net (code "167") (name "/LA14_P") (class "Default")
      (node (ref "J15") (pin "c18") (pinfunction "c18_c18") (pintype "bidirectional"))
    )
    (net (code "168") (name "/LA15_N") (class "Default")
      (node (ref "J15") (pin "h20") (pinfunction "h20_h20") (pintype "bidirectional"))
    )
    (net (code "169") (name "/LA15_P") (class "Default")
      (node (ref "J15") (pin "h19") (pinfunction "h19_h19") (pintype "bidirectional"))
    )
    (net (code "170") (name "/LA16_N") (class "Default")
      (node (ref "J15") (pin "g19") (pinfunction "g19_g19") (pintype "bidirectional"))
    )
    (net (code "171") (name "/LA16_P") (class "Default")
      (node (ref "J15") (pin "g18") (pinfunction "g18_g18") (pintype "bidirectional"))
    )
    (net (code "172") (name "/LA17_CC_N") (class "Default")
      (node (ref "J15") (pin "d21") (pinfunction "d21_d21") (pintype "bidirectional"))
    )
    (net (code "173") (name "/LA17_CC_P") (class "Default")
      (node (ref "J15") (pin "d20") (pinfunction "d20_d20") (pintype "bidirectional"))
    )
    (net (code "174") (name "/LA18_CC_N") (class "Default")
      (node (ref "J15") (pin "c23") (pinfunction "c23_c23") (pintype "bidirectional"))
    )
    (net (code "175") (name "/LA18_CC_P") (class "Default")
      (node (ref "J15") (pin "c22") (pinfunction "c22_c22") (pintype "bidirectional"))
    )
    (net (code "176") (name "/LA19_N") (class "Default")
      (node (ref "J15") (pin "h23") (pinfunction "h23_h23") (pintype "bidirectional"))
    )
    (net (code "177") (name "/LA19_P") (class "Default")
      (node (ref "J15") (pin "h22") (pinfunction "h22_h22") (pintype "bidirectional"))
    )
    (net (code "178") (name "/LA20_N") (class "Default")
      (node (ref "J15") (pin "g22") (pinfunction "g22_g22") (pintype "bidirectional"))
    )
    (net (code "179") (name "/LA20_P") (class "Default")
      (node (ref "J15") (pin "g21") (pinfunction "g21_g21") (pintype "bidirectional"))
    )
    (net (code "180") (name "/LA21_N") (class "Default")
      (node (ref "J15") (pin "h26") (pinfunction "h26_h26") (pintype "bidirectional"))
    )
    (net (code "181") (name "/LA21_P") (class "Default")
      (node (ref "J15") (pin "h25") (pinfunction "h25_h25") (pintype "bidirectional"))
    )
    (net (code "182") (name "/LA22_N") (class "Default")
      (node (ref "J15") (pin "g25") (pinfunction "g25_g25") (pintype "bidirectional"))
    )
    (net (code "183") (name "/LA22_P") (class "Default")
      (node (ref "J15") (pin "g24") (pinfunction "g24_g24") (pintype "bidirectional"))
    )
    (net (code "184") (name "/LA23_N") (class "Default")
      (node (ref "J15") (pin "d24") (pinfunction "d24_d24") (pintype "bidirectional"))
    )
    (net (code "185") (name "/LA23_P") (class "Default")
      (node (ref "J15") (pin "d23") (pinfunction "d23_d23") (pintype "bidirectional"))
    )
    (net (code "186") (name "/LA24_N") (class "Default")
      (node (ref "J15") (pin "h29") (pinfunction "h29_h29") (pintype "bidirectional"))
    )
    (net (code "187") (name "/LA24_P") (class "Default")
      (node (ref "J15") (pin "h28") (pinfunction "h28_h28") (pintype "bidirectional"))
    )
    (net (code "188") (name "/LA25_N") (class "Default")
      (node (ref "J15") (pin "g28") (pinfunction "g28_g28") (pintype "bidirectional"))
    )
    (net (code "189") (name "/LA25_P") (class "Default")
      (node (ref "J15") (pin "g27") (pinfunction "g27_g27") (pintype "bidirectional"))
    )
    (net (code "190") (name "/LA26_N") (class "Default")
      (node (ref "J15") (pin "d27") (pinfunction "d27_d27") (pintype "bidirectional"))
    )
    (net (code "191") (name "/LA26_P") (class "Default")
      (node (ref "J15") (pin "d26") (pinfunction "d26_d26") (pintype "bidirectional"))
    )
    (net (code "192") (name "/LA27_N") (class "Default")
      (node (ref "J15") (pin "c27") (pinfunction "c27_c27") (pintype "bidirectional"))
    )
    (net (code "193") (name "/LA27_P") (class "Default")
      (node (ref "J15") (pin "c26") (pinfunction "c26_c26") (pintype "bidirectional"))
    )
    (net (code "194") (name "/LA28_N") (class "Default")
      (node (ref "J15") (pin "h32") (pinfunction "h32_h32") (pintype "bidirectional"))
    )
    (net (code "195") (name "/LA28_P") (class "Default")
      (node (ref "J15") (pin "h31") (pinfunction "h31_h31") (pintype "bidirectional"))
    )
    (net (code "196") (name "/LA29_N") (class "Default")
      (node (ref "J15") (pin "g31") (pinfunction "g31_g31") (pintype "bidirectional"))
    )
    (net (code "197") (name "/LA29_P") (class "Default")
      (node (ref "J15") (pin "g30") (pinfunction "g30_g30") (pintype "bidirectional"))
    )
    (net (code "198") (name "/LA30_N") (class "Default")
      (node (ref "J15") (pin "h35") (pinfunction "h35_h35") (pintype "bidirectional"))
    )
    (net (code "199") (name "/LA30_P") (class "Default")
      (node (ref "J15") (pin "h34") (pinfunction "h34_h34") (pintype "bidirectional"))
    )
    (net (code "200") (name "/LA31_N") (class "Default")
      (node (ref "J15") (pin "g34") (pinfunction "g34_g34") (pintype "bidirectional"))
    )
    (net (code "201") (name "/LA31_P") (class "Default")
      (node (ref "J15") (pin "g33") (pinfunction "g33_g33") (pintype "bidirectional"))
    )
    (net (code "202") (name "/LA32_N") (class "Default")
      (node (ref "J15") (pin "h38") (pinfunction "h38_h38") (pintype "bidirectional"))
    )
    (net (code "203") (name "/LA32_P") (class "Default")
      (node (ref "J15") (pin "h37") (pinfunction "h37_h37") (pintype "bidirectional"))
    )
    (net (code "204") (name "/LA33_N") (class "Default")
      (node (ref "J15") (pin "g37") (pinfunction "g37_g37") (pintype "bidirectional"))
    )
    (net (code "205") (name "/LA33_P") (class "Default")
      (node (ref "J15") (pin "g36") (pinfunction "g36_g36") (pintype "bidirectional"))
    )
    (net (code "206") (name "/PG_C2M") (class "Default")
      (node (ref "J15") (pin "d1") (pinfunction "d1_d1") (pintype "bidirectional"))
    )
    (net (code "207") (name "/PG_M2C") (class "Default")
      (node (ref "J15") (pin "f1") (pinfunction "f1_f1") (pintype "bidirectional"))
    )
    (net (code "208") (name "/PRSNT_M2C_L") (class "Default")
      (node (ref "J15") (pin "h2") (pinfunction "h2_h2") (pintype "bidirectional"))
    )
    (net (code "209") (name "/SCL") (class "Default")
      (node (ref "J15") (pin "c30") (pinfunction "c30_c30") (pintype "bidirectional"))
    )
    (net (code "210") (name "/SDA") (class "Default")
      (node (ref "J15") (pin "c31") (pinfunction "c31_c31") (pintype "bidirectional"))
    )
    (net (code "211") (name "/TCK") (class "Default")
      (node (ref "J15") (pin "d29") (pinfunction "d29_d29") (pintype "bidirectional"))
    )
    (net (code "212") (name "/TDI") (class "Default")
      (node (ref "J15") (pin "d30") (pinfunction "d30_d30") (pintype "bidirectional"))
    )
    (net (code "213") (name "/TDO") (class "Default")
      (node (ref "J15") (pin "d31") (pinfunction "d31_d31") (pintype "bidirectional"))
    )
    (net (code "214") (name "/TMS") (class "Default")
      (node (ref "J15") (pin "d33") (pinfunction "d33_d33") (pintype "bidirectional"))
    )
    (net (code "215") (name "/TRST_L") (class "Default")
      (node (ref "J15") (pin "d34") (pinfunction "d34_d34") (pintype "bidirectional"))
    )
    (net (code "216") (name "/VADJ") (class "Default")
      (node (ref "C10") (pin "2") (pinfunction "2_2") (pintype "passive"))
      (node (ref "C7") (pin "1") (pinfunction "1_1") (pintype "passive"))
      (node (ref "C8") (pin "1") (pinfunction "1_1") (pintype "passive"))
      (node (ref "C9") (pin "1") (pinfunction "1_1") (pintype "passive"))
      (node (ref "J15") (pin "e39") (pinfunction "e39_e39") (pintype "bidirectional"))
      (node (ref "J15") (pin "f40") (pinfunction "f40_f40") (pintype "bidirectional"))
      (node (ref "J15") (pin "g39") (pinfunction "g39_g39") (pintype "bidirectional"))
      (node (ref "J15") (pin "h40") (pinfunction "h40_h40") (pintype "bidirectional"))
    )
    (net (code "218") (name "/VREF_A_M2C") (class "Default")
      (node (ref "J15") (pin "h1") (pinfunction "h1_h1") (pintype "bidirectional"))
    )
    (net (code "219") (name "/VREF_B_M2C") (class "Default")
      (node (ref "J15") (pin "k1") (pinfunction "k1_k1") (pintype "bidirectional"))
    )
    (net (code "231") (name "GND") (class "Default")
      (node (ref "B1") (pin "1") (pinfunction "1_1") (pintype "bidirectional"))
      (node (ref "B2") (pin "1") (pinfunction "1_1") (pintype "bidirectional"))
      (node (ref "B3") (pin "1") (pinfunction "1_1") (pintype "bidirectional"))
      (node (ref "B4") (pin "1") (pinfunction "1_1") (pintype "bidirectional"))
      (node (ref "C1") (pin "2") (pinfunction "2_2") (pintype "passive"))
      (node (ref "C10") (pin "1") (pinfunction "1_1") (pintype "passive"))
      (node (ref "C11") (pin "1") (pinfunction "1_1") (pintype "passive"))
      (node (ref "C12") (pin "2") (pinfunction "2_2") (pintype "passive"))
      (node (ref "C13") (pin "2") (pinfunction "2_2") (pintype "passive"))
      (node (ref "C14") (pin "2") (pinfunction "2_2") (pintype "passive"))
      (node (ref "C15") (pin "1") (pinfunction "1_1") (pintype "passive"))
      (node (ref "C16") (pin "2") (pinfunction "2_2") (pintype "passive"))
      (node (ref "C17") (pin "2") (pinfunction "2_2") (pintype "passive"))
      (node (ref "C2") (pin "2") (pinfunction "2_2") (pintype "passive"))
      (node (ref "C3") (pin "2") (pinfunction "2_2") (pintype "passive"))
      (node (ref "C4") (pin "1") (pinfunction "1_1") (pintype "passive"))
      (node (ref "C5") (pin "2") (pinfunction "2_2") (pintype "passive"))
      (node (ref "C6") (pin "1") (pinfunction "1_1") (pintype "passive"))
      (node (ref "C7") (pin "2") (pinfunction "2_2") (pintype "passive"))
      (node (ref "C8") (pin "2") (pinfunction "2_2") (pintype "passive"))
      (node (ref "C9") (pin "2") (pinfunction "2_2") (pintype "passive"))
      (node (ref "J15") (pin "a1") (pinfunction "a1_a1") (pintype "bidirectional"))
      (node (ref "J15") (pin "a12") (pinfunction "a12_a12") (pintype "bidirectional"))
      (node (ref "J15") (pin "a13") (pinfunction "a13_a13") (pintype "bidirectional"))
      (node (ref "J15") (pin "a16") (pinfunction "a16_a16") (pintype "bidirectional"))
      (node (ref "J15") (pin "a17") (pinfunction "a17_a17") (pintype "bidirectional"))
      (node (ref "J15") (pin "a20") (pinfunction "a20_a20") (pintype "bidirectional"))
      (node (ref "J15") (pin "a21") (pinfunction "a21_a21") (pintype "bidirectional"))
      (node (ref "J15") (pin "a24") (pinfunction "a24_a24") (pintype "bidirectional"))
      (node (ref "J15") (pin "a25") (pinfunction "a25_a25") (pintype "bidirectional"))
      (node (ref "J15") (pin "a28") (pinfunction "a28_a28") (pintype "bidirectional"))
      (node (ref "J15") (pin "a29") (pinfunction "a29_a29") (pintype "bidirectional"))
      (node (ref "J15") (pin "a32") (pinfunction "a32_a32") (pintype "bidirectional"))
      (node (ref "J15") (pin "a33") (pinfunction "a33_a33") (pintype "bidirectional"))
      (node (ref "J15") (pin "a36") (pinfunction "a36_a36") (pintype "bidirectional"))
      (node (ref "J15") (pin "a37") (pinfunction "a37_a37") (pintype "bidirectional"))
      (node (ref "J15") (pin "a4") (pinfunction "a4_a4") (pintype "bidirectional"))
      (node (ref "J15") (pin "a40") (pinfunction "a40_a40") (pintype "bidirectional"))
      (node (ref "J15") (pin "a5") (pinfunction "a5_a5") (pintype "bidirectional"))
      (node (ref "J15") (pin "a8") (pinfunction "a8_a8") (pintype "bidirectional"))
      (node (ref "J15") (pin "a9") (pinfunction "a9_a9") (pintype "bidirectional"))
      (node (ref "J15") (pin "b10") (pinfunction "b10_b10") (pintype "bidirectional"))
      (node (ref "J15") (pin "b11") (pinfunction "b11_b11") (pintype "bidirectional"))
      (node (ref "J15") (pin "b14") (pinfunction "b14_b14") (pintype "bidirectional"))
      (node (ref "J15") (pin "b15") (pinfunction "b15_b15") (pintype "bidirectional"))
      (node (ref "J15") (pin "b18") (pinfunction "b18_b18") (pintype "bidirectional"))
      (node (ref "J15") (pin "b19") (pinfunction "b19_b19") (pintype "bidirectional"))
      (node (ref "J15") (pin "b2") (pinfunction "b2_b2") (pintype "bidirectional"))
      (node (ref "J15") (pin "b22") (pinfunction "b22_b22") (pintype "bidirectional"))
      (node (ref "J15") (pin "b23") (pinfunction "b23_b23") (pintype "bidirectional"))
      (node (ref "J15") (pin "b26") (pinfunction "b26_b26") (pintype "bidirectional"))
      (node (ref "J15") (pin "b27") (pinfunction "b27_b27") (pintype "bidirectional"))
      (node (ref "J15") (pin "b3") (pinfunction "b3_b3") (pintype "bidirectional"))
      (node (ref "J15") (pin "b30") (pinfunction "b30_b30") (pintype "bidirectional"))
      (node (ref "J15") (pin "b31") (pinfunction "b31_b31") (pintype "bidirectional"))
      (node (ref "J15") (pin "b34") (pinfunction "b34_b34") (pintype "bidirectional"))
      (node (ref "J15") (pin "b35") (pinfunction "b35_b35") (pintype "bidirectional"))
      (node (ref "J15") (pin "b38") (pinfunction "b38_b38") (pintype "bidirectional"))
      (node (ref "J15") (pin "b39") (pinfunction "b39_b39") (pintype "bidirectional"))
      (node (ref "J15") (pin "b6") (pinfunction "b6_b6") (pintype "bidirectional"))
      (node (ref "J15") (pin "b7") (pinfunction "b7_b7") (pintype "bidirectional"))
      (node (ref "J15") (pin "c1") (pinfunction "c1_c1") (pintype "bidirectional"))
      (node (ref "J15") (pin "c12") (pinfunction "c12_c12") (pintype "bidirectional"))
      (node (ref "J15") (pin "c13") (pinfunction "c13_c13") (pintype "bidirectional"))
      (node (ref "J15") (pin "c16") (pinfunction "c16_c16") (pintype "bidirectional"))
      (node (ref "J15") (pin "c17") (pinfunction "c17_c17") (pintype "bidirectional"))
      (node (ref "J15") (pin "c20") (pinfunction "c20_c20") (pintype "bidirectional"))
      (node (ref "J15") (pin "c21") (pinfunction "c21_c21") (pintype "bidirectional"))
      (node (ref "J15") (pin "c24") (pinfunction "c24_c24") (pintype "bidirectional"))
      (node (ref "J15") (pin "c25") (pinfunction "c25_c25") (pintype "bidirectional"))
      (node (ref "J15") (pin "c28") (pinfunction "c28_c28") (pintype "bidirectional"))
      (node (ref "J15") (pin "c29") (pinfunction "c29_c29") (pintype "bidirectional"))
      (node (ref "J15") (pin "c32") (pinfunction "c32_c32") (pintype "bidirectional"))
      (node (ref "J15") (pin "c33") (pinfunction "c33_c33") (pintype "bidirectional"))
      (node (ref "J15") (pin "c36") (pinfunction "c36_c36") (pintype "bidirectional"))
      (node (ref "J15") (pin "c38") (pinfunction "c38_c38") (pintype "bidirectional"))
      (node (ref "J15") (pin "c4") (pinfunction "c4_c4") (pintype "bidirectional"))
      (node (ref "J15") (pin "c40") (pinfunction "c40_c40") (pintype "bidirectional"))
      (node (ref "J15") (pin "c5") (pinfunction "c5_c5") (pintype "bidirectional"))
      (node (ref "J15") (pin "c8") (pinfunction "c8_c8") (pintype "bidirectional"))
      (node (ref "J15") (pin "c9") (pinfunction "c9_c9") (pintype "bidirectional"))
      (node (ref "J15") (pin "d10") (pinfunction "d10_d10") (pintype "bidirectional"))
      (node (ref "J15") (pin "d13") (pinfunction "d13_d13") (pintype "bidirectional"))
      (node (ref "J15") (pin "d16") (pinfunction "d16_d16") (pintype "bidirectional"))
      (node (ref "J15") (pin "d19") (pinfunction "d19_d19") (pintype "bidirectional"))
      (node (ref "J15") (pin "d2") (pinfunction "d2_d2") (pintype "bidirectional"))
      (node (ref "J15") (pin "d22") (pinfunction "d22_d22") (pintype "bidirectional"))
      (node (ref "J15") (pin "d25") (pinfunction "d25_d25") (pintype "bidirectional"))
      (node (ref "J15") (pin "d28") (pinfunction "d28_d28") (pintype "bidirectional"))
      (node (ref "J15") (pin "d3") (pinfunction "d3_d3") (pintype "bidirectional"))
      (node (ref "J15") (pin "d37") (pinfunction "d37_d37") (pintype "bidirectional"))
      (node (ref "J15") (pin "d39") (pinfunction "d39_d39") (pintype "bidirectional"))
      (node (ref "J15") (pin "d6") (pinfunction "d6_d6") (pintype "bidirectional"))
      (node (ref "J15") (pin "d7") (pinfunction "d7_d7") (pintype "bidirectional"))
      (node (ref "J15") (pin "e1") (pinfunction "e1_e1") (pintype "bidirectional"))
      (node (ref "J15") (pin "e11") (pinfunction "e11_e11") (pintype "bidirectional"))
      (node (ref "J15") (pin "e14") (pinfunction "e14_e14") (pintype "bidirectional"))
      (node (ref "J15") (pin "e17") (pinfunction "e17_e17") (pintype "bidirectional"))
      (node (ref "J15") (pin "e20") (pinfunction "e20_e20") (pintype "bidirectional"))
      (node (ref "J15") (pin "e23") (pinfunction "e23_e23") (pintype "bidirectional"))
      (node (ref "J15") (pin "e26") (pinfunction "e26_e26") (pintype "bidirectional"))
      (node (ref "J15") (pin "e29") (pinfunction "e29_e29") (pintype "bidirectional"))
      (node (ref "J15") (pin "e32") (pinfunction "e32_e32") (pintype "bidirectional"))
      (node (ref "J15") (pin "e35") (pinfunction "e35_e35") (pintype "bidirectional"))
      (node (ref "J15") (pin "e38") (pinfunction "e38_e38") (pintype "bidirectional"))
      (node (ref "J15") (pin "e4") (pinfunction "e4_e4") (pintype "bidirectional"))
      (node (ref "J15") (pin "e40") (pinfunction "e40_e40") (pintype "bidirectional"))
      (node (ref "J15") (pin "e5") (pinfunction "e5_e5") (pintype "bidirectional"))
      (node (ref "J15") (pin "e8") (pinfunction "e8_e8") (pintype "bidirectional"))
      (node (ref "J15") (pin "f12") (pinfunction "f12_f12") (pintype "bidirectional"))
      (node (ref "J15") (pin "f15") (pinfunction "f15_f15") (pintype "bidirectional"))
      (node (ref "J15") (pin "f18") (pinfunction "f18_f18") (pintype "bidirectional"))
      (node (ref "J15") (pin "f2") (pinfunction "f2_f2") (pintype "bidirectional"))
      (node (ref "J15") (pin "f21") (pinfunction "f21_f21") (pintype "bidirectional"))
      (node (ref "J15") (pin "f24") (pinfunction "f24_f24") (pintype "bidirectional"))
      (node (ref "J15") (pin "f27") (pinfunction "f27_f27") (pintype "bidirectional"))
      (node (ref "J15") (pin "f3") (pinfunction "f3_f3") (pintype "bidirectional"))
      (node (ref "J15") (pin "f30") (pinfunction "f30_f30") (pintype "bidirectional"))
      (node (ref "J15") (pin "f33") (pinfunction "f33_f33") (pintype "bidirectional"))
      (node (ref "J15") (pin "f36") (pinfunction "f36_f36") (pintype "bidirectional"))
      (node (ref "J15") (pin "f39") (pinfunction "f39_f39") (pintype "bidirectional"))
      (node (ref "J15") (pin "f6") (pinfunction "f6_f6") (pintype "bidirectional"))
      (node (ref "J15") (pin "f9") (pinfunction "f9_f9") (pintype "bidirectional"))
      (node (ref "J15") (pin "g1") (pinfunction "g1_g1") (pintype "bidirectional"))
      (node (ref "J15") (pin "g11") (pinfunction "g11_g11") (pintype "bidirectional"))
      (node (ref "J15") (pin "g14") (pinfunction "g14_g14") (pintype "bidirectional"))
      (node (ref "J15") (pin "g17") (pinfunction "g17_g17") (pintype "bidirectional"))
      (node (ref "J15") (pin "g20") (pinfunction "g20_g20") (pintype "bidirectional"))
      (node (ref "J15") (pin "g23") (pinfunction "g23_g23") (pintype "bidirectional"))
      (node (ref "J15") (pin "g26") (pinfunction "g26_g26") (pintype "bidirectional"))
      (node (ref "J15") (pin "g29") (pinfunction "g29_g29") (pintype "bidirectional"))
      (node (ref "J15") (pin "g32") (pinfunction "g32_g32") (pintype "bidirectional"))
      (node (ref "J15") (pin "g35") (pinfunction "g35_g35") (pintype "bidirectional"))
      (node (ref "J15") (pin "g38") (pinfunction "g38_g38") (pintype "bidirectional"))
      (node (ref "J15") (pin "g4") (pinfunction "g4_g4") (pintype "bidirectional"))
      (node (ref "J15") (pin "g40") (pinfunction "g40_g40") (pintype "bidirectional"))
      (node (ref "J15") (pin "g5") (pinfunction "g5_g5") (pintype "bidirectional"))
      (node (ref "J15") (pin "g8") (pinfunction "g8_g8") (pintype "bidirectional"))
      (node (ref "J15") (pin "h12") (pinfunction "h12_h12") (pintype "bidirectional"))
      (node (ref "J15") (pin "h15") (pinfunction "h15_h15") (pintype "bidirectional"))
      (node (ref "J15") (pin "h18") (pinfunction "h18_h18") (pintype "bidirectional"))
      (node (ref "J15") (pin "h21") (pinfunction "h21_h21") (pintype "bidirectional"))
      (node (ref "J15") (pin "h24") (pinfunction "h24_h24") (pintype "bidirectional"))
      (node (ref "J15") (pin "h27") (pinfunction "h27_h27") (pintype "bidirectional"))
      (node (ref "J15") (pin "h3") (pinfunction "h3_h3") (pintype "bidirectional"))
      (node (ref "J15") (pin "h30") (pinfunction "h30_h30") (pintype "bidirectional"))
      (node (ref "J15") (pin "h33") (pinfunction "h33_h33") (pintype "bidirectional"))
      (node (ref "J15") (pin "h36") (pinfunction "h36_h36") (pintype "bidirectional"))
      (node (ref "J15") (pin "h39") (pinfunction "h39_h39") (pintype "bidirectional"))
      (node (ref "J15") (pin "h6") (pinfunction "h6_h6") (pintype "bidirectional"))
      (node (ref "J15") (pin "h9") (pinfunction "h9_h9") (pintype "bidirectional"))
      (node (ref "J15") (pin "j1") (pinfunction "j1_j1") (pintype "bidirectional"))
      (node (ref "J15") (pin "j11") (pinfunction "j11_j11") (pintype "bidirectional"))
      (node (ref "J15") (pin "j14") (pinfunction "j14_j14") (pintype "bidirectional"))
      (node (ref "J15") (pin "j17") (pinfunction "j17_j17") (pintype "bidirectional"))
      (node (ref "J15") (pin "j20") (pinfunction "j20_j20") (pintype "bidirectional"))
      (node (ref "J15") (pin "j23") (pinfunction "j23_j23") (pintype "bidirectional"))
      (node (ref "J15") (pin "j26") (pinfunction "j26_j26") (pintype "bidirectional"))
      (node (ref "J15") (pin "j29") (pinfunction "j29_j29") (pintype "bidirectional"))
      (node (ref "J15") (pin "j32") (pinfunction "j32_j32") (pintype "bidirectional"))
      (node (ref "J15") (pin "j35") (pinfunction "j35_j35") (pintype "bidirectional"))
      (node (ref "J15") (pin "j38") (pinfunction "j38_j38") (pintype "bidirectional"))
      (node (ref "J15") (pin "j4") (pinfunction "j4_j4") (pintype "bidirectional"))
      (node (ref "J15") (pin "j40") (pinfunction "j40_j40") (pintype "bidirectional"))
      (node (ref "J15") (pin "j5") (pinfunction "j5_j5") (pintype "bidirectional"))
      (node (ref "J15") (pin "j8") (pinfunction "j8_j8") (pintype "bidirectional"))
      (node (ref "J15") (pin "k12") (pinfunction "k12_k12") (pintype "bidirectional"))
      (node (ref "J15") (pin "k15") (pinfunction "k15_k15") (pintype "bidirectional"))
      (node (ref "J15") (pin "k18") (pinfunction "k18_k18") (pintype "bidirectional"))
      (node (ref "J15") (pin "k2") (pinfunction "k2_k2") (pintype "bidirectional"))
      (node (ref "J15") (pin "k21") (pinfunction "k21_k21") (pintype "bidirectional"))
      (node (ref "J15") (pin "k24") (pinfunction "k24_k24") (pintype "bidirectional"))
      (node (ref "J15") (pin "k27") (pinfunction "k27_k27") (pintype "bidirectional"))
      (node (ref "J15") (pin "k3") (pinfunction "k3_k3") (pintype "bidirectional"))
      (node (ref "J15") (pin "k30") (pinfunction "k30_k30") (pintype "bidirectional"))
      (node (ref "J15") (pin "k33") (pinfunction "k33_k33") (pintype "bidirectional"))
      (node (ref "J15") (pin "k36") (pinfunction "k36_k36") (pintype "bidirectional"))
      (node (ref "J15") (pin "k39") (pinfunction "k39_k39") (pintype "bidirectional"))
      (node (ref "J15") (pin "k6") (pinfunction "k6_k6") (pintype "bidirectional"))
      (node (ref "J15") (pin "k9") (pinfunction "k9_k9") (pintype "bidirectional"))
    )
    (net (code "232") (name "unconnected-(J15-Pada14)") (class "Default")
      (node (ref "J15") (pin "a14") (pinfunction "a14_a14") (pintype "bidirectional"))
    )
    (net (code "233") (name "unconnected-(J15-Pada15)") (class "Default")
      (node (ref "J15") (pin "a15") (pinfunction "a15_a15") (pintype "bidirectional"))
    )
    (net (code "234") (name "unconnected-(J15-Pada18)") (class "Default")
      (node (ref "J15") (pin "a18") (pinfunction "a18_a18") (pintype "bidirectional"))
    )
    (net (code "235") (name "unconnected-(J15-Pada19)") (class "Default")
      (node (ref "J15") (pin "a19") (pinfunction "a19_a19") (pintype "bidirectional"))
    )
    (net (code "236") (name "unconnected-(J15-Pada34)") (class "Default")
      (node (ref "J15") (pin "a34") (pinfunction "a34_a34") (pintype "bidirectional"))
    )
    (net (code "237") (name "unconnected-(J15-Pada35)") (class "Default")
      (node (ref "J15") (pin "a35") (pinfunction "a35_a35") (pintype "bidirectional"))
    )
    (net (code "238") (name "unconnected-(J15-Pada38)") (class "Default")
      (node (ref "J15") (pin "a38") (pinfunction "a38_a38") (pintype "bidirectional"))
    )
    (net (code "239") (name "unconnected-(J15-Pada39)") (class "Default")
      (node (ref "J15") (pin "a39") (pinfunction "a39_a39") (pintype "bidirectional"))
    )
    (net (code "240") (name "unconnected-(J15-Padb4)") (class "Default")
      (node (ref "J15") (pin "b4") (pinfunction "b4_b4") (pintype "bidirectional"))
    )
    (net (code "241") (name "unconnected-(J15-Padb5)") (class "Default")
      (node (ref "J15") (pin "b5") (pinfunction "b5_b5") (pintype "bidirectional"))
    )
    (net (code "242") (name "unconnected-(J15-Padb8)") (class "Default")
      (node (ref "J15") (pin "b8") (pinfunction "b8_b8") (pintype "bidirectional"))
    )
    (net (code "243") (name "unconnected-(J15-Padb9)") (class "Default")
      (node (ref "J15") (pin "b9") (pinfunction "b9_b9") (pintype "bidirectional"))
    )
    (net (code "244") (name "unconnected-(J15-Padb12)") (class "Default")
      (node (ref "J15") (pin "b12") (pinfunction "b12_b12") (pintype "bidirectional"))
    )
    (net (code "245") (name "unconnected-(J15-Padb13)") (class "Default")
      (node (ref "J15") (pin "b13") (pinfunction "b13_b13") (pintype "bidirectional"))
    )
    (net (code "246") (name "unconnected-(J15-Padb16)") (class "Default")
      (node (ref "J15") (pin "b16") (pinfunction "b16_b16") (pintype "bidirectional"))
    )
    (net (code "247") (name "unconnected-(J15-Padb17)") (class "Default")
      (node (ref "J15") (pin "b17") (pinfunction "b17_b17") (pintype "bidirectional"))
    )
    (net (code "248") (name "unconnected-(J15-Padb24)") (class "Default")
      (node (ref "J15") (pin "b24") (pinfunction "b24_b24") (pintype "bidirectional"))
    )
    (net (code "249") (name "unconnected-(J15-Padb25)") (class "Default")
      (node (ref "J15") (pin "b25") (pinfunction "b25_b25") (pintype "bidirectional"))
    )
    (net (code "250") (name "unconnected-(J15-Padb28)") (class "Default")
      (node (ref "J15") (pin "b28") (pinfunction "b28_b28") (pintype "bidirectional"))
    )
    (net (code "251") (name "unconnected-(J15-Padb29)") (class "Default")
      (node (ref "J15") (pin "b29") (pinfunction "b29_b29") (pintype "bidirectional"))
    )
    (net (code "252") (name "unconnected-(J15-Padb32)") (class "Default")
      (node (ref "J15") (pin "b32") (pinfunction "b32_b32") (pintype "bidirectional"))
    )
    (net (code "253") (name "unconnected-(J15-Padb33)") (class "Default")
      (node (ref "J15") (pin "b33") (pinfunction "b33_b33") (pintype "bidirectional"))
    )
    (net (code "254") (name "unconnected-(J15-Padb36)") (class "Default")
      (node (ref "J15") (pin "b36") (pinfunction "b36_b36") (pintype "bidirectional"))
    )
    (net (code "255") (name "unconnected-(J15-Padb37)") (class "Default")
      (node (ref "J15") (pin "b37") (pinfunction "b37_b37") (pintype "bidirectional"))
    )
    (net (code "256") (name "unconnected-(J15-Padb40)") (class "Default")
      (node (ref "J15") (pin "b40") (pinfunction "b40_b40") (pintype "bidirectional"))
    )
    (net (code "257") (name "unconnected-(J15-Padj39)") (class "Default")
      (node (ref "J15") (pin "j39") (pinfunction "j39_j39") (pintype "bidirectional"))
    )
    (net (code "258") (name "unconnected-(J15-Padk40)") (class "Default")
      (node (ref "J15") (pin "k40") (pinfunction "k40_k40") (pintype "bidirectional"))
    )
  )
)
